# Hotkeys.net
KiCad netlist of a schematic drawn in EAGLE
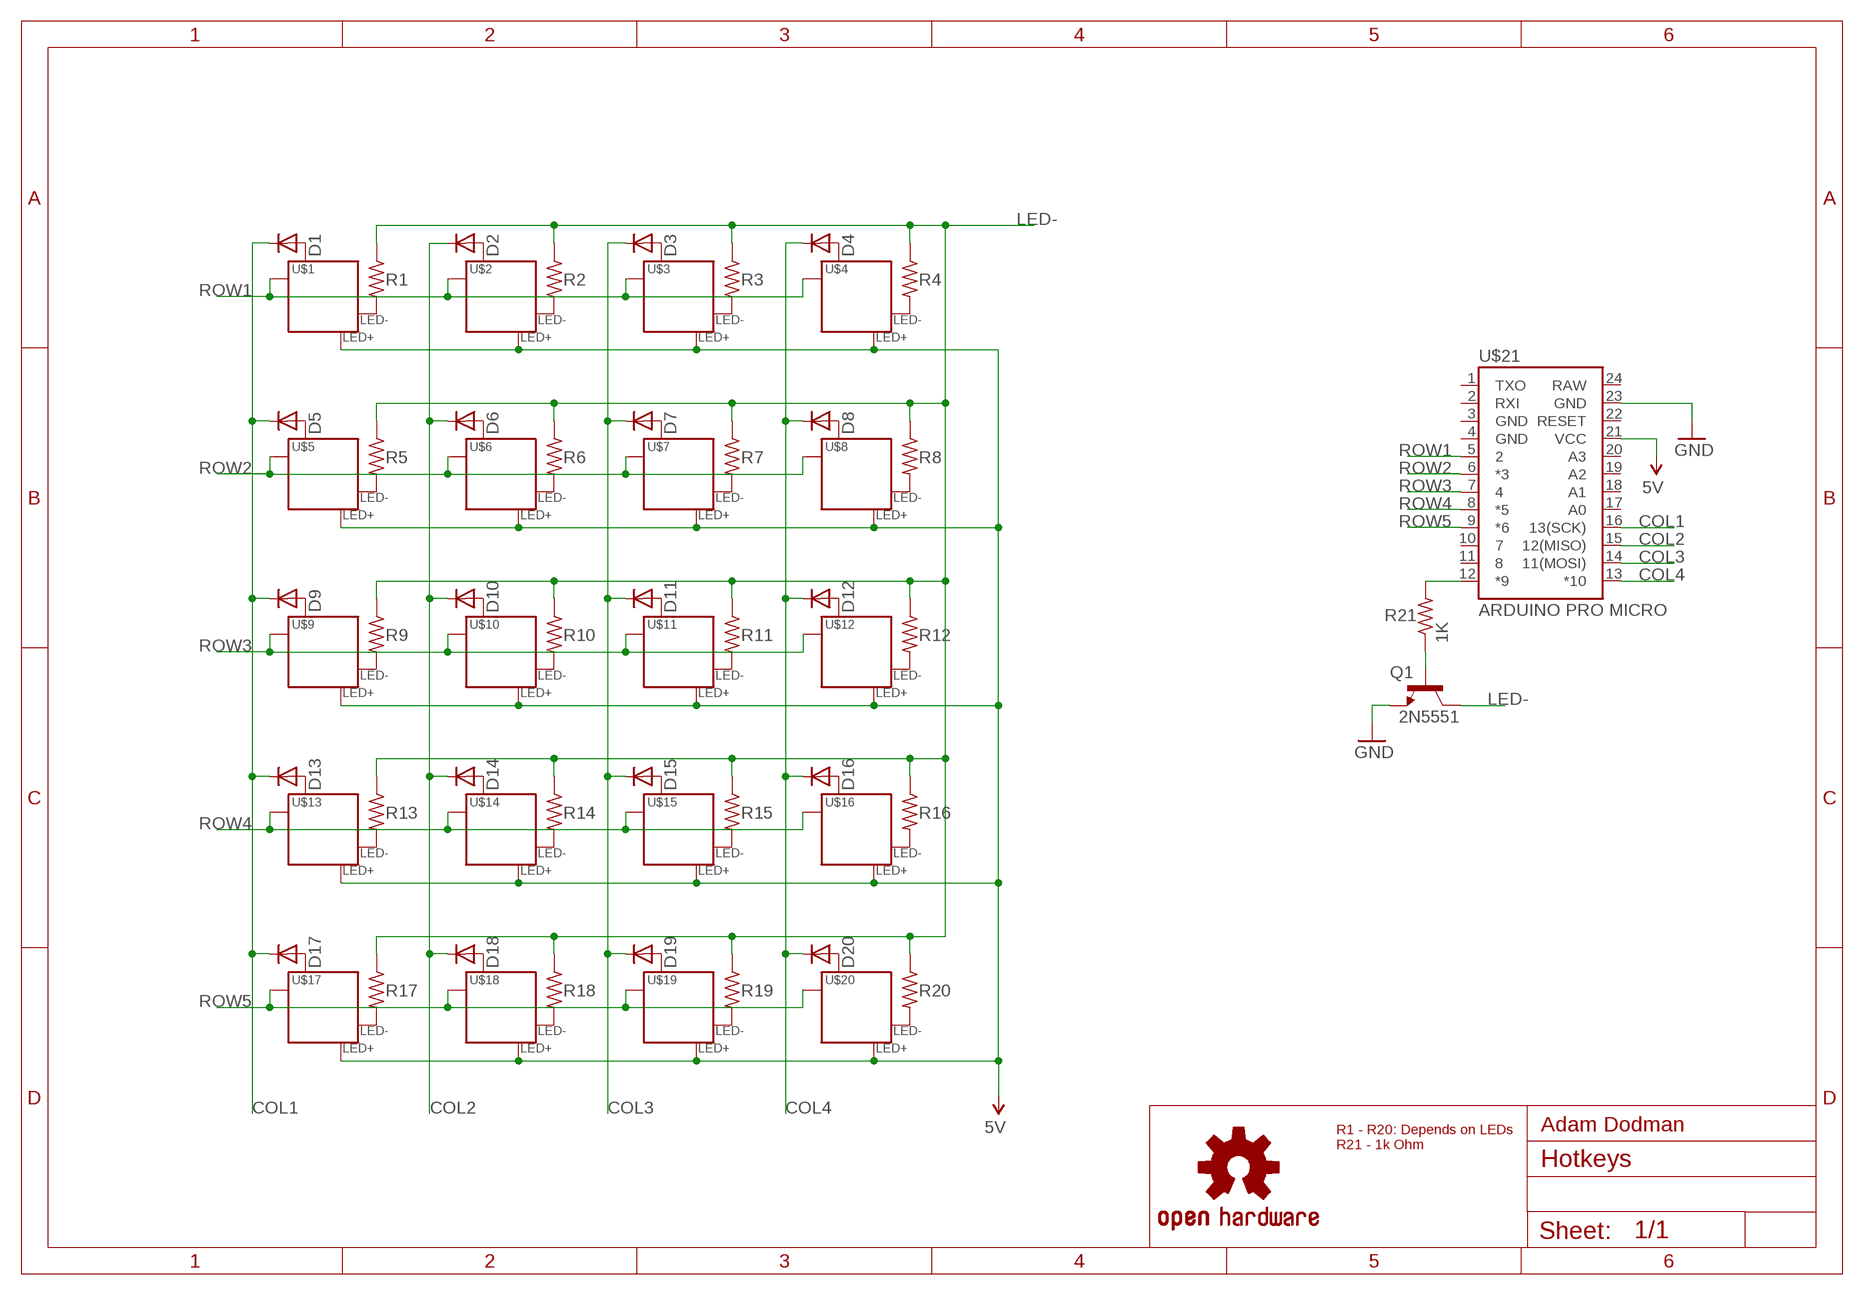
[diagram p0: schematic, sheet 1]

(export (version "E")
  (design (tool "Eeschema 10.0.6"))
  (components
    (comp (ref "D1")
      (value "DIODE-DO41-7.6")
      (footprint "eagle-import:DO41-7.6")
      (libsource (lib "eagle-import") (part "DIODE-DO41-7.6"))
    )
    (comp (ref "D2")
      (value "DIODE-DO41-7.6")
      (footprint "eagle-import:DO41-7.6")
      (libsource (lib "eagle-import") (part "DIODE-DO41-7.6"))
    )
    (comp (ref "D3")
      (value "DIODE-DO41-7.6")
      (footprint "eagle-import:DO41-7.6")
      (libsource (lib "eagle-import") (part "DIODE-DO41-7.6"))
    )
    (comp (ref "D4")
      (value "DIODE-DO41-7.6")
      (footprint "eagle-import:DO41-7.6")
      (libsource (lib "eagle-import") (part "DIODE-DO41-7.6"))
    )
    (comp (ref "D5")
      (value "DIODE-DO41-7.6")
      (footprint "eagle-import:DO41-7.6")
      (libsource (lib "eagle-import") (part "DIODE-DO41-7.6"))
    )
    (comp (ref "D6")
      (value "DIODE-DO41-7.6")
      (footprint "eagle-import:DO41-7.6")
      (libsource (lib "eagle-import") (part "DIODE-DO41-7.6"))
    )
    (comp (ref "D7")
      (value "DIODE-DO41-7.6")
      (footprint "eagle-import:DO41-7.6")
      (libsource (lib "eagle-import") (part "DIODE-DO41-7.6"))
    )
    (comp (ref "D8")
      (value "DIODE-DO41-7.6")
      (footprint "eagle-import:DO41-7.6")
      (libsource (lib "eagle-import") (part "DIODE-DO41-7.6"))
    )
    (comp (ref "D9")
      (value "DIODE-DO41-7.6")
      (footprint "eagle-import:DO41-7.6")
      (libsource (lib "eagle-import") (part "DIODE-DO41-7.6"))
    )
    (comp (ref "D10")
      (value "DIODE-DO41-7.6")
      (footprint "eagle-import:DO41-7.6")
      (libsource (lib "eagle-import") (part "DIODE-DO41-7.6"))
    )
    (comp (ref "D11")
      (value "DIODE-DO41-7.6")
      (footprint "eagle-import:DO41-7.6")
      (libsource (lib "eagle-import") (part "DIODE-DO41-7.6"))
    )
    (comp (ref "D12")
      (value "DIODE-DO41-7.6")
      (footprint "eagle-import:DO41-7.6")
      (libsource (lib "eagle-import") (part "DIODE-DO41-7.6"))
    )
    (comp (ref "D13")
      (value "DIODE-DO41-7.6")
      (footprint "eagle-import:DO41-7.6")
      (libsource (lib "eagle-import") (part "DIODE-DO41-7.6"))
    )
    (comp (ref "D14")
      (value "DIODE-DO41-7.6")
      (footprint "eagle-import:DO41-7.6")
      (libsource (lib "eagle-import") (part "DIODE-DO41-7.6"))
    )
    (comp (ref "D15")
      (value "DIODE-DO41-7.6")
      (footprint "eagle-import:DO41-7.6")
      (libsource (lib "eagle-import") (part "DIODE-DO41-7.6"))
    )
    (comp (ref "D16")
      (value "DIODE-DO41-7.6")
      (footprint "eagle-import:DO41-7.6")
      (libsource (lib "eagle-import") (part "DIODE-DO41-7.6"))
    )
    (comp (ref "D17")
      (value "DIODE-DO41-7.6")
      (footprint "eagle-import:DO41-7.6")
      (libsource (lib "eagle-import") (part "DIODE-DO41-7.6"))
    )
    (comp (ref "D18")
      (value "DIODE-DO41-7.6")
      (footprint "eagle-import:DO41-7.6")
      (libsource (lib "eagle-import") (part "DIODE-DO41-7.6"))
    )
    (comp (ref "D19")
      (value "DIODE-DO41-7.6")
      (footprint "eagle-import:DO41-7.6")
      (libsource (lib "eagle-import") (part "DIODE-DO41-7.6"))
    )
    (comp (ref "D20")
      (value "DIODE-DO41-7.6")
      (footprint "eagle-import:DO41-7.6")
      (libsource (lib "eagle-import") (part "DIODE-DO41-7.6"))
    )
    (comp (ref "LOGO1")
      (value "OSHW-LOGOM")
      (footprint "eagle-import:OSHW-LOGO-M")
      (libsource (lib "eagle-import") (part "OSHW-LOGOM"))
    )
    (comp (ref "Q1")
      (value "2N5551")
      (footprint "eagle-import:TO-92-AMMO")
      (libsource (lib "eagle-import") (part "TRANSISTOR_NPNBC547"))
    )
    (comp (ref "R1")
      (value "R-US_0207/7")
      (footprint "eagle-import:0207_7")
      (libsource (lib "eagle-import") (part "R-US_0207/7"))
    )
    (comp (ref "R2")
      (value "R-US_0207/7")
      (footprint "eagle-import:0207_7")
      (libsource (lib "eagle-import") (part "R-US_0207/7"))
    )
    (comp (ref "R3")
      (value "R-US_0207/7")
      (footprint "eagle-import:0207_7")
      (libsource (lib "eagle-import") (part "R-US_0207/7"))
    )
    (comp (ref "R4")
      (value "R-US_0207/7")
      (footprint "eagle-import:0207_7")
      (libsource (lib "eagle-import") (part "R-US_0207/7"))
    )
    (comp (ref "R5")
      (value "R-US_0207/7")
      (footprint "eagle-import:0207_7")
      (libsource (lib "eagle-import") (part "R-US_0207/7"))
    )
    (comp (ref "R6")
      (value "R-US_0207/7")
      (footprint "eagle-import:0207_7")
      (libsource (lib "eagle-import") (part "R-US_0207/7"))
    )
    (comp (ref "R7")
      (value "R-US_0207/7")
      (footprint "eagle-import:0207_7")
      (libsource (lib "eagle-import") (part "R-US_0207/7"))
    )
    (comp (ref "R8")
      (value "R-US_0207/7")
      (footprint "eagle-import:0207_7")
      (libsource (lib "eagle-import") (part "R-US_0207/7"))
    )
    (comp (ref "R9")
      (value "R-US_0207/7")
      (footprint "eagle-import:0207_7")
      (libsource (lib "eagle-import") (part "R-US_0207/7"))
    )
    (comp (ref "R10")
      (value "R-US_0207/7")
      (footprint "eagle-import:0207_7")
      (libsource (lib "eagle-import") (part "R-US_0207/7"))
    )
    (comp (ref "R11")
      (value "R-US_0207/7")
      (footprint "eagle-import:0207_7")
      (libsource (lib "eagle-import") (part "R-US_0207/7"))
    )
    (comp (ref "R12")
      (value "R-US_0207/7")
      (footprint "eagle-import:0207_7")
      (libsource (lib "eagle-import") (part "R-US_0207/7"))
    )
    (comp (ref "R13")
      (value "R-US_0207/7")
      (footprint "eagle-import:0207_7")
      (libsource (lib "eagle-import") (part "R-US_0207/7"))
    )
    (comp (ref "R14")
      (value "R-US_0207/7")
      (footprint "eagle-import:0207_7")
      (libsource (lib "eagle-import") (part "R-US_0207/7"))
    )
    (comp (ref "R15")
      (value "R-US_0207/7")
      (footprint "eagle-import:0207_7")
      (libsource (lib "eagle-import") (part "R-US_0207/7"))
    )
    (comp (ref "R16")
      (value "R-US_0207/7")
      (footprint "eagle-import:0207_7")
      (libsource (lib "eagle-import") (part "R-US_0207/7"))
    )
    (comp (ref "R17")
      (value "R-US_0207/7")
      (footprint "eagle-import:0207_7")
      (libsource (lib "eagle-import") (part "R-US_0207/7"))
    )
    (comp (ref "R18")
      (value "R-US_0207/7")
      (footprint "eagle-import:0207_7")
      (libsource (lib "eagle-import") (part "R-US_0207/7"))
    )
    (comp (ref "R19")
      (value "R-US_0207/7")
      (footprint "eagle-import:0207_7")
      (libsource (lib "eagle-import") (part "R-US_0207/7"))
    )
    (comp (ref "R20")
      (value "R-US_0207/7")
      (footprint "eagle-import:0207_7")
      (libsource (lib "eagle-import") (part "R-US_0207/7"))
    )
    (comp (ref "R21")
      (value "1K")
      (footprint "eagle-import:0207_7")
      (libsource (lib "eagle-import") (part "R-US_0207/7"))
    )
    (comp (ref "U$1")
      (value "MX-1U-LED")
      (footprint "eagle-import:P-MX-1U-LED")
      (libsource (lib "eagle-import") (part "MX-1U-LED"))
    )
    (comp (ref "U$2")
      (value "MX-1U-LED")
      (footprint "eagle-import:P-MX-1U-LED")
      (libsource (lib "eagle-import") (part "MX-1U-LED"))
    )
    (comp (ref "U$3")
      (value "MX-1U-LED")
      (footprint "eagle-import:P-MX-1U-LED")
      (libsource (lib "eagle-import") (part "MX-1U-LED"))
    )
    (comp (ref "U$4")
      (value "MX-1U-LED")
      (footprint "eagle-import:P-MX-1U-LED")
      (libsource (lib "eagle-import") (part "MX-1U-LED"))
    )
    (comp (ref "U$5")
      (value "MX-1U-LED")
      (footprint "eagle-import:P-MX-1U-LED")
      (libsource (lib "eagle-import") (part "MX-1U-LED"))
    )
    (comp (ref "U$6")
      (value "MX-1U-LED")
      (footprint "eagle-import:P-MX-1U-LED")
      (libsource (lib "eagle-import") (part "MX-1U-LED"))
    )
    (comp (ref "U$7")
      (value "MX-1U-LED")
      (footprint "eagle-import:P-MX-1U-LED")
      (libsource (lib "eagle-import") (part "MX-1U-LED"))
    )
    (comp (ref "U$8")
      (value "MX-1U-LED")
      (footprint "eagle-import:P-MX-1U-LED")
      (libsource (lib "eagle-import") (part "MX-1U-LED"))
    )
    (comp (ref "U$9")
      (value "MX-1U-LED")
      (footprint "eagle-import:P-MX-1U-LED")
      (libsource (lib "eagle-import") (part "MX-1U-LED"))
    )
    (comp (ref "U$10")
      (value "MX-1U-LED")
      (footprint "eagle-import:P-MX-1U-LED")
      (libsource (lib "eagle-import") (part "MX-1U-LED"))
    )
    (comp (ref "U$11")
      (value "MX-1U-LED")
      (footprint "eagle-import:P-MX-1U-LED")
      (libsource (lib "eagle-import") (part "MX-1U-LED"))
    )
    (comp (ref "U$12")
      (value "MX-1U-LED")
      (footprint "eagle-import:P-MX-1U-LED")
      (libsource (lib "eagle-import") (part "MX-1U-LED"))
    )
    (comp (ref "U$13")
      (value "MX-1U-LED")
      (footprint "eagle-import:P-MX-1U-LED")
      (libsource (lib "eagle-import") (part "MX-1U-LED"))
    )
    (comp (ref "U$14")
      (value "MX-1U-LED")
      (footprint "eagle-import:P-MX-1U-LED")
      (libsource (lib "eagle-import") (part "MX-1U-LED"))
    )
    (comp (ref "U$15")
      (value "MX-1U-LED")
      (footprint "eagle-import:P-MX-1U-LED")
      (libsource (lib "eagle-import") (part "MX-1U-LED"))
    )
    (comp (ref "U$16")
      (value "MX-1U-LED")
      (footprint "eagle-import:P-MX-1U-LED")
      (libsource (lib "eagle-import") (part "MX-1U-LED"))
    )
    (comp (ref "U$17")
      (value "MX-1U-LED")
      (footprint "eagle-import:P-MX-1U-LED")
      (libsource (lib "eagle-import") (part "MX-1U-LED"))
    )
    (comp (ref "U$18")
      (value "MX-1U-LED")
      (footprint "eagle-import:P-MX-1U-LED")
      (libsource (lib "eagle-import") (part "MX-1U-LED"))
    )
    (comp (ref "U$19")
      (value "MX-1U-LED")
      (footprint "eagle-import:P-MX-1U-LED")
      (libsource (lib "eagle-import") (part "MX-1U-LED"))
    )
    (comp (ref "U$20")
      (value "MX-1U-LED")
      (footprint "eagle-import:P-MX-1U-LED")
      (libsource (lib "eagle-import") (part "MX-1U-LED"))
    )
    (comp (ref "U$21")
      (value "ARDUINO PRO MICRO")
      (footprint "eagle-import:ARDUINO_PRO_MICRO")
      (libsource (lib "eagle-import") (part "ARDUINO_PRO_MICRO"))
    )
  )
  (nets
    (net (code "1") (name "/COL1") (class "Default")
      (node (ref "D1") (pin "C") (pinfunction "C_C") (pintype "passive"))
      (node (ref "D13") (pin "C") (pinfunction "C_C") (pintype "passive"))
      (node (ref "D17") (pin "C") (pinfunction "C_C") (pintype "passive"))
      (node (ref "D5") (pin "C") (pinfunction "C_C") (pintype "passive"))
      (node (ref "D9") (pin "C") (pinfunction "C_C") (pintype "passive"))
      (node (ref "U$21") (pin "16") (pinfunction "13(SCK)_16") (pintype "bidirectional"))
    )
    (net (code "2") (name "/COL2") (class "Default")
      (node (ref "D10") (pin "C") (pinfunction "C_C") (pintype "passive"))
      (node (ref "D14") (pin "C") (pinfunction "C_C") (pintype "passive"))
      (node (ref "D18") (pin "C") (pinfunction "C_C") (pintype "passive"))
      (node (ref "D2") (pin "C") (pinfunction "C_C") (pintype "passive"))
      (node (ref "D6") (pin "C") (pinfunction "C_C") (pintype "passive"))
      (node (ref "U$21") (pin "15") (pinfunction "12(MISO)_15") (pintype "bidirectional"))
    )
    (net (code "3") (name "/COL3") (class "Default")
      (node (ref "D11") (pin "C") (pinfunction "C_C") (pintype "passive"))
      (node (ref "D15") (pin "C") (pinfunction "C_C") (pintype "passive"))
      (node (ref "D19") (pin "C") (pinfunction "C_C") (pintype "passive"))
      (node (ref "D3") (pin "C") (pinfunction "C_C") (pintype "passive"))
      (node (ref "D7") (pin "C") (pinfunction "C_C") (pintype "passive"))
      (node (ref "U$21") (pin "14") (pinfunction "11(MOSI)_14") (pintype "bidirectional"))
    )
    (net (code "4") (name "/COL4") (class "Default")
      (node (ref "D12") (pin "C") (pinfunction "C_C") (pintype "passive"))
      (node (ref "D16") (pin "C") (pinfunction "C_C") (pintype "passive"))
      (node (ref "D20") (pin "C") (pinfunction "C_C") (pintype "passive"))
      (node (ref "D4") (pin "C") (pinfunction "C_C") (pintype "passive"))
      (node (ref "D8") (pin "C") (pinfunction "C_C") (pintype "passive"))
      (node (ref "U$21") (pin "13") (pinfunction "*10_13") (pintype "bidirectional"))
    )
    (net (code "5") (name "/LED-") (class "Default")
      (node (ref "Q1") (pin "1") (pinfunction "C_1") (pintype "passive"))
      (node (ref "R1") (pin "1") (pinfunction "1_1") (pintype "passive"))
      (node (ref "R10") (pin "1") (pinfunction "1_1") (pintype "passive"))
      (node (ref "R11") (pin "1") (pinfunction "1_1") (pintype "passive"))
      (node (ref "R12") (pin "1") (pinfunction "1_1") (pintype "passive"))
      (node (ref "R13") (pin "1") (pinfunction "1_1") (pintype "passive"))
      (node (ref "R14") (pin "1") (pinfunction "1_1") (pintype "passive"))
      (node (ref "R15") (pin "1") (pinfunction "1_1") (pintype "passive"))
      (node (ref "R16") (pin "1") (pinfunction "1_1") (pintype "passive"))
      (node (ref "R17") (pin "1") (pinfunction "1_1") (pintype "passive"))
      (node (ref "R18") (pin "1") (pinfunction "1_1") (pintype "passive"))
      (node (ref "R19") (pin "1") (pinfunction "1_1") (pintype "passive"))
      (node (ref "R2") (pin "1") (pinfunction "1_1") (pintype "passive"))
      (node (ref "R20") (pin "1") (pinfunction "1_1") (pintype "passive"))
      (node (ref "R3") (pin "1") (pinfunction "1_1") (pintype "passive"))
      (node (ref "R4") (pin "1") (pinfunction "1_1") (pintype "passive"))
      (node (ref "R5") (pin "1") (pinfunction "1_1") (pintype "passive"))
      (node (ref "R6") (pin "1") (pinfunction "1_1") (pintype "passive"))
      (node (ref "R7") (pin "1") (pinfunction "1_1") (pintype "passive"))
      (node (ref "R8") (pin "1") (pinfunction "1_1") (pintype "passive"))
      (node (ref "R9") (pin "1") (pinfunction "1_1") (pintype "passive"))
    )
    (net (code "6") (name "/ROW1") (class "Default")
      (node (ref "U$1") (pin "MX1") (pinfunction "P0_MX1") (pintype "bidirectional"))
      (node (ref "U$2") (pin "MX1") (pinfunction "P0_MX1") (pintype "bidirectional"))
      (node (ref "U$21") (pin "5") (pinfunction "2_5") (pintype "bidirectional"))
      (node (ref "U$3") (pin "MX1") (pinfunction "P0_MX1") (pintype "bidirectional"))
      (node (ref "U$4") (pin "MX1") (pinfunction "P0_MX1") (pintype "bidirectional"))
    )
    (net (code "7") (name "/ROW2") (class "Default")
      (node (ref "U$21") (pin "6") (pinfunction "*3_6") (pintype "bidirectional"))
      (node (ref "U$5") (pin "MX1") (pinfunction "P0_MX1") (pintype "bidirectional"))
      (node (ref "U$6") (pin "MX1") (pinfunction "P0_MX1") (pintype "bidirectional"))
      (node (ref "U$7") (pin "MX1") (pinfunction "P0_MX1") (pintype "bidirectional"))
      (node (ref "U$8") (pin "MX1") (pinfunction "P0_MX1") (pintype "bidirectional"))
    )
    (net (code "8") (name "/ROW3") (class "Default")
      (node (ref "U$10") (pin "MX1") (pinfunction "P0_MX1") (pintype "bidirectional"))
      (node (ref "U$11") (pin "MX1") (pinfunction "P0_MX1") (pintype "bidirectional"))
      (node (ref "U$12") (pin "MX1") (pinfunction "P0_MX1") (pintype "bidirectional"))
      (node (ref "U$21") (pin "7") (pinfunction "4_7") (pintype "bidirectional"))
      (node (ref "U$9") (pin "MX1") (pinfunction "P0_MX1") (pintype "bidirectional"))
    )
    (net (code "9") (name "/ROW4") (class "Default")
      (node (ref "U$13") (pin "MX1") (pinfunction "P0_MX1") (pintype "bidirectional"))
      (node (ref "U$14") (pin "MX1") (pinfunction "P0_MX1") (pintype "bidirectional"))
      (node (ref "U$15") (pin "MX1") (pinfunction "P0_MX1") (pintype "bidirectional"))
      (node (ref "U$16") (pin "MX1") (pinfunction "P0_MX1") (pintype "bidirectional"))
      (node (ref "U$21") (pin "8") (pinfunction "*5_8") (pintype "bidirectional"))
    )
    (net (code "10") (name "/ROW5") (class "Default")
      (node (ref "U$17") (pin "MX1") (pinfunction "P0_MX1") (pintype "bidirectional"))
      (node (ref "U$18") (pin "MX1") (pinfunction "P0_MX1") (pintype "bidirectional"))
      (node (ref "U$19") (pin "MX1") (pinfunction "P0_MX1") (pintype "bidirectional"))
      (node (ref "U$20") (pin "MX1") (pinfunction "P0_MX1") (pintype "bidirectional"))
      (node (ref "U$21") (pin "9") (pinfunction "*6_9") (pintype "bidirectional"))
    )
    (net (code "11") (name "5V") (class "Default")
      (node (ref "U$1") (pin "LED+") (pinfunction "LED+_LED+") (pintype "bidirectional"))
      (node (ref "U$10") (pin "LED+") (pinfunction "LED+_LED+") (pintype "bidirectional"))
      (node (ref "U$11") (pin "LED+") (pinfunction "LED+_LED+") (pintype "bidirectional"))
      (node (ref "U$12") (pin "LED+") (pinfunction "LED+_LED+") (pintype "bidirectional"))
      (node (ref "U$13") (pin "LED+") (pinfunction "LED+_LED+") (pintype "bidirectional"))
      (node (ref "U$14") (pin "LED+") (pinfunction "LED+_LED+") (pintype "bidirectional"))
      (node (ref "U$15") (pin "LED+") (pinfunction "LED+_LED+") (pintype "bidirectional"))
      (node (ref "U$16") (pin "LED+") (pinfunction "LED+_LED+") (pintype "bidirectional"))
      (node (ref "U$17") (pin "LED+") (pinfunction "LED+_LED+") (pintype "bidirectional"))
      (node (ref "U$18") (pin "LED+") (pinfunction "LED+_LED+") (pintype "bidirectional"))
      (node (ref "U$19") (pin "LED+") (pinfunction "LED+_LED+") (pintype "bidirectional"))
      (node (ref "U$2") (pin "LED+") (pinfunction "LED+_LED+") (pintype "bidirectional"))
      (node (ref "U$20") (pin "LED+") (pinfunction "LED+_LED+") (pintype "bidirectional"))
      (node (ref "U$21") (pin "21") (pinfunction "VCC_21") (pintype "bidirectional"))
      (node (ref "U$3") (pin "LED+") (pinfunction "LED+_LED+") (pintype "bidirectional"))
      (node (ref "U$4") (pin "LED+") (pinfunction "LED+_LED+") (pintype "bidirectional"))
      (node (ref "U$5") (pin "LED+") (pinfunction "LED+_LED+") (pintype "bidirectional"))
      (node (ref "U$6") (pin "LED+") (pinfunction "LED+_LED+") (pintype "bidirectional"))
      (node (ref "U$7") (pin "LED+") (pinfunction "LED+_LED+") (pintype "bidirectional"))
      (node (ref "U$8") (pin "LED+") (pinfunction "LED+_LED+") (pintype "bidirectional"))
      (node (ref "U$9") (pin "LED+") (pinfunction "LED+_LED+") (pintype "bidirectional"))
    )
    (net (code "12") (name "GND") (class "Default")
      (node (ref "Q1") (pin "3") (pinfunction "E_3") (pintype "passive"))
      (node (ref "U$21") (pin "23") (pinfunction "GND_23") (pintype "bidirectional"))
    )
    (net (code "13") (name "Net-(Q1-B)") (class "Default")
      (node (ref "Q1") (pin "2") (pinfunction "B_2") (pintype "passive"))
      (node (ref "R21") (pin "1") (pinfunction "1_1") (pintype "passive"))
    )
    (net (code "14") (name "Net-(R1-Pad2)") (class "Default")
      (node (ref "R1") (pin "2") (pinfunction "2_2") (pintype "passive"))
      (node (ref "U$1") (pin "LED-") (pinfunction "LED-_LED-") (pintype "bidirectional"))
    )
    (net (code "15") (name "Net-(R2-Pad2)") (class "Default")
      (node (ref "R2") (pin "2") (pinfunction "2_2") (pintype "passive"))
      (node (ref "U$2") (pin "LED-") (pinfunction "LED-_LED-") (pintype "bidirectional"))
    )
    (net (code "16") (name "Net-(R3-Pad2)") (class "Default")
      (node (ref "R3") (pin "2") (pinfunction "2_2") (pintype "passive"))
      (node (ref "U$3") (pin "LED-") (pinfunction "LED-_LED-") (pintype "bidirectional"))
    )
    (net (code "17") (name "Net-(R4-Pad2)") (class "Default")
      (node (ref "R4") (pin "2") (pinfunction "2_2") (pintype "passive"))
      (node (ref "U$4") (pin "LED-") (pinfunction "LED-_LED-") (pintype "bidirectional"))
    )
    (net (code "18") (name "Net-(R5-Pad2)") (class "Default")
      (node (ref "R5") (pin "2") (pinfunction "2_2") (pintype "passive"))
      (node (ref "U$5") (pin "LED-") (pinfunction "LED-_LED-") (pintype "bidirectional"))
    )
    (net (code "19") (name "Net-(R6-Pad2)") (class "Default")
      (node (ref "R6") (pin "2") (pinfunction "2_2") (pintype "passive"))
      (node (ref "U$6") (pin "LED-") (pinfunction "LED-_LED-") (pintype "bidirectional"))
    )
    (net (code "20") (name "Net-(R7-Pad2)") (class "Default")
      (node (ref "R7") (pin "2") (pinfunction "2_2") (pintype "passive"))
      (node (ref "U$7") (pin "LED-") (pinfunction "LED-_LED-") (pintype "bidirectional"))
    )
    (net (code "21") (name "Net-(R8-Pad2)") (class "Default")
      (node (ref "R8") (pin "2") (pinfunction "2_2") (pintype "passive"))
      (node (ref "U$8") (pin "LED-") (pinfunction "LED-_LED-") (pintype "bidirectional"))
    )
    (net (code "22") (name "Net-(R9-Pad2)") (class "Default")
      (node (ref "R9") (pin "2") (pinfunction "2_2") (pintype "passive"))
      (node (ref "U$9") (pin "LED-") (pinfunction "LED-_LED-") (pintype "bidirectional"))
    )
    (net (code "23") (name "Net-(R10-Pad2)") (class "Default")
      (node (ref "R10") (pin "2") (pinfunction "2_2") (pintype "passive"))
      (node (ref "U$10") (pin "LED-") (pinfunction "LED-_LED-") (pintype "bidirectional"))
    )
    (net (code "24") (name "Net-(R11-Pad2)") (class "Default")
      (node (ref "R11") (pin "2") (pinfunction "2_2") (pintype "passive"))
      (node (ref "U$11") (pin "LED-") (pinfunction "LED-_LED-") (pintype "bidirectional"))
    )
    (net (code "25") (name "Net-(R12-Pad2)") (class "Default")
      (node (ref "R12") (pin "2") (pinfunction "2_2") (pintype "passive"))
      (node (ref "U$12") (pin "LED-") (pinfunction "LED-_LED-") (pintype "bidirectional"))
    )
    (net (code "26") (name "Net-(R13-Pad2)") (class "Default")
      (node (ref "R13") (pin "2") (pinfunction "2_2") (pintype "passive"))
      (node (ref "U$13") (pin "LED-") (pinfunction "LED-_LED-") (pintype "bidirectional"))
    )
    (net (code "27") (name "Net-(R14-Pad2)") (class "Default")
      (node (ref "R14") (pin "2") (pinfunction "2_2") (pintype "passive"))
      (node (ref "U$14") (pin "LED-") (pinfunction "LED-_LED-") (pintype "bidirectional"))
    )
    (net (code "28") (name "Net-(R15-Pad2)") (class "Default")
      (node (ref "R15") (pin "2") (pinfunction "2_2") (pintype "passive"))
      (node (ref "U$15") (pin "LED-") (pinfunction "LED-_LED-") (pintype "bidirectional"))
    )
    (net (code "29") (name "Net-(R16-Pad2)") (class "Default")
      (node (ref "R16") (pin "2") (pinfunction "2_2") (pintype "passive"))
      (node (ref "U$16") (pin "LED-") (pinfunction "LED-_LED-") (pintype "bidirectional"))
    )
    (net (code "30") (name "Net-(R17-Pad2)") (class "Default")
      (node (ref "R17") (pin "2") (pinfunction "2_2") (pintype "passive"))
      (node (ref "U$17") (pin "LED-") (pinfunction "LED-_LED-") (pintype "bidirectional"))
    )
    (net (code "31") (name "Net-(R18-Pad2)") (class "Default")
      (node (ref "R18") (pin "2") (pinfunction "2_2") (pintype "passive"))
      (node (ref "U$18") (pin "LED-") (pinfunction "LED-_LED-") (pintype "bidirectional"))
    )
    (net (code "32") (name "Net-(R19-Pad2)") (class "Default")
      (node (ref "R19") (pin "2") (pinfunction "2_2") (pintype "passive"))
      (node (ref "U$19") (pin "LED-") (pinfunction "LED-_LED-") (pintype "bidirectional"))
    )
    (net (code "33") (name "Net-(R20-Pad2)") (class "Default")
      (node (ref "R20") (pin "2") (pinfunction "2_2") (pintype "passive"))
      (node (ref "U$20") (pin "LED-") (pinfunction "LED-_LED-") (pintype "bidirectional"))
    )
    (net (code "34") (name "Net-(U$1-P1)") (class "Default")
      (node (ref "D1") (pin "A") (pinfunction "A_A") (pintype "passive"))
      (node (ref "U$1") (pin "MX2") (pinfunction "P1_MX2") (pintype "bidirectional"))
    )
    (net (code "35") (name "Net-(U$2-P1)") (class "Default")
      (node (ref "D2") (pin "A") (pinfunction "A_A") (pintype "passive"))
      (node (ref "U$2") (pin "MX2") (pinfunction "P1_MX2") (pintype "bidirectional"))
    )
    (net (code "36") (name "Net-(U$3-P1)") (class "Default")
      (node (ref "D3") (pin "A") (pinfunction "A_A") (pintype "passive"))
      (node (ref "U$3") (pin "MX2") (pinfunction "P1_MX2") (pintype "bidirectional"))
    )
    (net (code "37") (name "Net-(U$4-P1)") (class "Default")
      (node (ref "D4") (pin "A") (pinfunction "A_A") (pintype "passive"))
      (node (ref "U$4") (pin "MX2") (pinfunction "P1_MX2") (pintype "bidirectional"))
    )
    (net (code "38") (name "Net-(U$5-P1)") (class "Default")
      (node (ref "D5") (pin "A") (pinfunction "A_A") (pintype "passive"))
      (node (ref "U$5") (pin "MX2") (pinfunction "P1_MX2") (pintype "bidirectional"))
    )
    (net (code "39") (name "Net-(U$6-P1)") (class "Default")
      (node (ref "D6") (pin "A") (pinfunction "A_A") (pintype "passive"))
      (node (ref "U$6") (pin "MX2") (pinfunction "P1_MX2") (pintype "bidirectional"))
    )
    (net (code "40") (name "Net-(U$7-P1)") (class "Default")
      (node (ref "D7") (pin "A") (pinfunction "A_A") (pintype "passive"))
      (node (ref "U$7") (pin "MX2") (pinfunction "P1_MX2") (pintype "bidirectional"))
    )
    (net (code "41") (name "Net-(U$8-P1)") (class "Default")
      (node (ref "D8") (pin "A") (pinfunction "A_A") (pintype "passive"))
      (node (ref "U$8") (pin "MX2") (pinfunction "P1_MX2") (pintype "bidirectional"))
    )
    (net (code "42") (name "Net-(U$9-P1)") (class "Default")
      (node (ref "D9") (pin "A") (pinfunction "A_A") (pintype "passive"))
      (node (ref "U$9") (pin "MX2") (pinfunction "P1_MX2") (pintype "bidirectional"))
    )
    (net (code "43") (name "Net-(U$10-P1)") (class "Default")
      (node (ref "D10") (pin "A") (pinfunction "A_A") (pintype "passive"))
      (node (ref "U$10") (pin "MX2") (pinfunction "P1_MX2") (pintype "bidirectional"))
    )
    (net (code "44") (name "Net-(U$11-P1)") (class "Default")
      (node (ref "D11") (pin "A") (pinfunction "A_A") (pintype "passive"))
      (node (ref "U$11") (pin "MX2") (pinfunction "P1_MX2") (pintype "bidirectional"))
    )
    (net (code "45") (name "Net-(U$12-P1)") (class "Default")
      (node (ref "D12") (pin "A") (pinfunction "A_A") (pintype "passive"))
      (node (ref "U$12") (pin "MX2") (pinfunction "P1_MX2") (pintype "bidirectional"))
    )
    (net (code "46") (name "Net-(U$13-P1)") (class "Default")
      (node (ref "D13") (pin "A") (pinfunction "A_A") (pintype "passive"))
      (node (ref "U$13") (pin "MX2") (pinfunction "P1_MX2") (pintype "bidirectional"))
    )
    (net (code "47") (name "Net-(U$14-P1)") (class "Default")
      (node (ref "D14") (pin "A") (pinfunction "A_A") (pintype "passive"))
      (node (ref "U$14") (pin "MX2") (pinfunction "P1_MX2") (pintype "bidirectional"))
    )
    (net (code "48") (name "Net-(U$15-P1)") (class "Default")
      (node (ref "D15") (pin "A") (pinfunction "A_A") (pintype "passive"))
      (node (ref "U$15") (pin "MX2") (pinfunction "P1_MX2") (pintype "bidirectional"))
    )
    (net (code "49") (name "Net-(U$16-P1)") (class "Default")
      (node (ref "D16") (pin "A") (pinfunction "A_A") (pintype "passive"))
      (node (ref "U$16") (pin "MX2") (pinfunction "P1_MX2") (pintype "bidirectional"))
    )
    (net (code "50") (name "Net-(U$17-P1)") (class "Default")
      (node (ref "D17") (pin "A") (pinfunction "A_A") (pintype "passive"))
      (node (ref "U$17") (pin "MX2") (pinfunction "P1_MX2") (pintype "bidirectional"))
    )
    (net (code "51") (name "Net-(U$18-P1)") (class "Default")
      (node (ref "D18") (pin "A") (pinfunction "A_A") (pintype "passive"))
      (node (ref "U$18") (pin "MX2") (pinfunction "P1_MX2") (pintype "bidirectional"))
    )
    (net (code "52") (name "Net-(U$19-P1)") (class "Default")
      (node (ref "D19") (pin "A") (pinfunction "A_A") (pintype "passive"))
      (node (ref "U$19") (pin "MX2") (pinfunction "P1_MX2") (pintype "bidirectional"))
    )
    (net (code "53") (name "Net-(U$20-P1)") (class "Default")
      (node (ref "D20") (pin "A") (pinfunction "A_A") (pintype "passive"))
      (node (ref "U$20") (pin "MX2") (pinfunction "P1_MX2") (pintype "bidirectional"))
    )
    (net (code "54") (name "Net-(U$21-*9)") (class "Default")
      (node (ref "R21") (pin "2") (pinfunction "2_2") (pintype "passive"))
      (node (ref "U$21") (pin "12") (pinfunction "*9_12") (pintype "bidirectional"))
    )
    (net (code "55") (name "unconnected-(U$21-7-Pad10)") (class "Default")
      (node (ref "U$21") (pin "10") (pinfunction "7_10") (pintype "bidirectional"))
    )
    (net (code "56") (name "unconnected-(U$21-8-Pad11)") (class "Default")
      (node (ref "U$21") (pin "11") (pinfunction "8_11") (pintype "bidirectional"))
    )
    (net (code "57") (name "unconnected-(U$21-A0-Pad17)") (class "Default")
      (node (ref "U$21") (pin "17") (pinfunction "A0_17") (pintype "bidirectional"))
    )
    (net (code "58") (name "unconnected-(U$21-A1-Pad18)") (class "Default")
      (node (ref "U$21") (pin "18") (pinfunction "A1_18") (pintype "bidirectional"))
    )
    (net (code "59") (name "unconnected-(U$21-A2-Pad19)") (class "Default")
      (node (ref "U$21") (pin "19") (pinfunction "A2_19") (pintype "bidirectional"))
    )
    (net (code "60") (name "unconnected-(U$21-A3-Pad20)") (class "Default")
      (node (ref "U$21") (pin "20") (pinfunction "A3_20") (pintype "bidirectional"))
    )
    (net (code "61") (name "unconnected-(U$21-GND-Pad3)") (class "Default")
      (node (ref "U$21") (pin "3") (pinfunction "GND_3") (pintype "bidirectional"))
    )
    (net (code "62") (name "unconnected-(U$21-GND-Pad4)") (class "Default")
      (node (ref "U$21") (pin "4") (pinfunction "GND_4") (pintype "bidirectional"))
    )
    (net (code "63") (name "unconnected-(U$21-RAW-Pad24)") (class "Default")
      (node (ref "U$21") (pin "24") (pinfunction "RAW_24") (pintype "bidirectional"))
    )
    (net (code "64") (name "unconnected-(U$21-RESET-Pad22)") (class "Default")
      (node (ref "U$21") (pin "22") (pinfunction "RESET_22") (pintype "bidirectional"))
    )
    (net (code "65") (name "unconnected-(U$21-RXI-Pad2)") (class "Default")
      (node (ref "U$21") (pin "2") (pinfunction "RXI_2") (pintype "bidirectional"))
    )
    (net (code "66") (name "unconnected-(U$21-TXO-Pad1)") (class "Default")
      (node (ref "U$21") (pin "1") (pinfunction "TXO_1") (pintype "bidirectional"))
    )
  )
)
